# STB_USB.net
KiCad netlist of a schematic drawn in Altium Designer
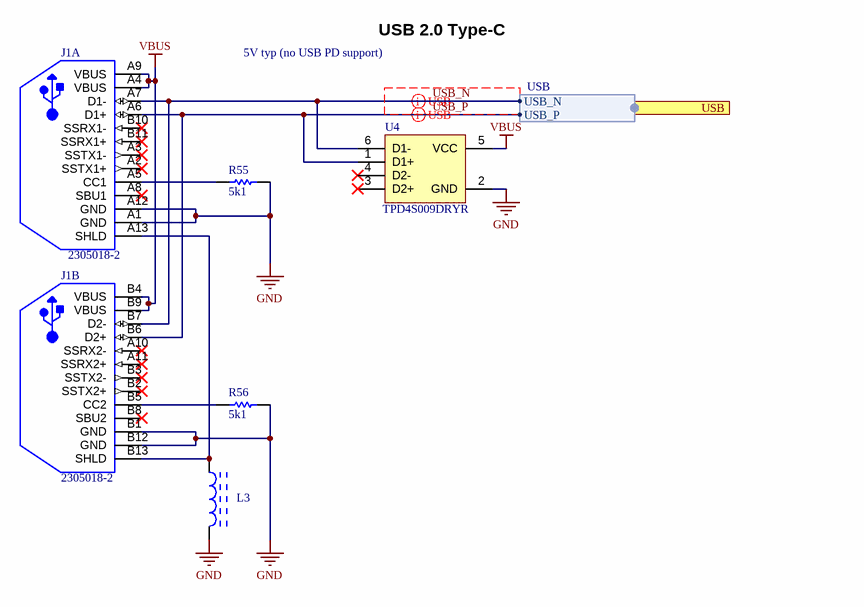
[diagram p0: STB_USB.SchDoc]

(export (version "E")
  (design (tool "Eeschema 10.0.6"))
  (components
    (comp (ref "J1")
      (value "2305018-2")
      (footprint "2305018-2")
      (description "USB TYPE C, REC IPX8 ON BOARD DUAL SMT")
      (fields (field (name "MANUFACTURER") "TE Connectivity"))
      (libsource (lib "") (part "632723300011_1"))
    )
    (comp (ref "L3")
      (value "LI0402E300R-10")
      (footprint "INDC1005X07L")
      (description "30 Ohm 1 Power, Signal Line Ferrite Bead 0402 (1005 Metric) 500mA 300 mOhm Max DCR")
      (fields (field (name "MANUFACTURER") "Laird-Signal Integrity Products"))
      (libsource (lib "ETHZ Vault") (part "Ferrite Bead"))
    )
    (comp (ref "R55")
      (value "5k1")
      (footprint "RESC1005X40X25LL05T10")
      (fields
        (field (name "PART NUMBER") "RC0402FR-075K1L")
        (field (name "MANUFACTURER") "Yageo / Phycomp")
        (field (name "TOLERANCE") "1%")
      )
      (libsource (lib "Altium Content Vault") (part "RES"))
    )
    (comp (ref "R56")
      (value "5k1")
      (footprint "RESC1005X40X25LL05T10")
      (fields
        (field (name "PART NUMBER") "RC0402FR-075K1L")
        (field (name "MANUFACTURER") "Yageo / Phycomp")
        (field (name "TOLERANCE") "1%")
      )
      (libsource (lib "Altium Content Vault") (part "RES"))
    )
    (comp (ref "U4")
      (value "TPD4S009DRYR")
      (footprint "DRY0006A")
      (fields (field (name "MANUFACTURER") "Texas Instruments"))
      (libsource (lib "Altium Content Vault") (part "TI-TPD4S009-SON_DRY-6"))
    )
  )
  (nets
    (net (code "2") (name "/USB_N") (class "Default")
      (node (ref "J1") (pin "A7") (pinfunction "D1-_A7") (pintype "bidirectional"))
      (node (ref "J1") (pin "B7") (pinfunction "D2-_B7") (pintype "bidirectional"))
      (node (ref "U4") (pin "6") (pinfunction "D1-_6") (pintype "passive"))
    )
    (net (code "3") (name "/USB_P") (class "Default")
      (node (ref "J1") (pin "A6") (pinfunction "D1+_A6") (pintype "bidirectional"))
      (node (ref "J1") (pin "B6") (pinfunction "D2+_B6") (pintype "bidirectional"))
      (node (ref "U4") (pin "1") (pinfunction "D1+_1") (pintype "passive"))
    )
    (net (code "5") (name "GND") (class "Default")
      (node (ref "J1") (pin "A1") (pinfunction "GND_A1") (pintype "power_in"))
      (node (ref "J1") (pin "A12") (pinfunction "GND_A12") (pintype "power_in"))
      (node (ref "J1") (pin "B1") (pinfunction "GND_B1") (pintype "power_in"))
      (node (ref "J1") (pin "B12") (pinfunction "GND_B12") (pintype "power_in"))
      (node (ref "L3") (pin "2") (pinfunction "2_2") (pintype "passive"))
      (node (ref "R55") (pin "1") (pinfunction "1_1") (pintype "passive"))
      (node (ref "R56") (pin "1") (pinfunction "1_1") (pintype "passive"))
      (node (ref "U4") (pin "2") (pinfunction "GND_2") (pintype "power_in"))
    )
    (net (code "6") (name "Net-(J1A-CC1)") (class "Default")
      (node (ref "J1") (pin "A5") (pinfunction "CC1_A5") (pintype "passive"))
      (node (ref "R55") (pin "2") (pinfunction "2_2") (pintype "passive"))
    )
    (net (code "7") (name "Net-(J1A-SHLD)") (class "Default")
      (node (ref "J1") (pin "A13") (pinfunction "SHLD_A13") (pintype "power_in"))
      (node (ref "J1") (pin "B13") (pinfunction "SHLD_B13") (pintype "power_in"))
      (node (ref "L3") (pin "1") (pinfunction "1_1") (pintype "passive"))
    )
    (net (code "8") (name "Net-(J1B-CC2)") (class "Default")
      (node (ref "J1") (pin "B5") (pinfunction "CC2_B5") (pintype "passive"))
      (node (ref "R56") (pin "2") (pinfunction "2_2") (pintype "passive"))
    )
    (net (code "9") (name "VBUS") (class "Default")
      (node (ref "J1") (pin "A4") (pinfunction "VBUS_A4") (pintype "power_in"))
      (node (ref "J1") (pin "A9") (pinfunction "VBUS_A9") (pintype "power_in"))
      (node (ref "J1") (pin "B4") (pinfunction "VBUS_B4") (pintype "power_in"))
      (node (ref "J1") (pin "B9") (pinfunction "VBUS_B9") (pintype "power_in"))
      (node (ref "U4") (pin "5") (pinfunction "VCC_5") (pintype "power_in"))
    )
    (net (code "10") (name "unconnected-(J1A-SBU1-PadA8)") (class "Default")
      (node (ref "J1") (pin "A8") (pinfunction "SBU1_A8") (pintype "passive+no_connect"))
    )
    (net (code "11") (name "unconnected-(J1A-SSRX1+-PadB11)") (class "Default")
      (node (ref "J1") (pin "B11") (pinfunction "SSRX1+_B11") (pintype "input+no_connect"))
    )
    (net (code "12") (name "unconnected-(J1A-SSRX1--PadB10)") (class "Default")
      (node (ref "J1") (pin "B10") (pinfunction "SSRX1-_B10") (pintype "input+no_connect"))
    )
    (net (code "13") (name "unconnected-(J1A-SSTX1+-PadA2)") (class "Default")
      (node (ref "J1") (pin "A2") (pinfunction "SSTX1+_A2") (pintype "output+no_connect"))
    )
    (net (code "14") (name "unconnected-(J1A-SSTX1--PadA3)") (class "Default")
      (node (ref "J1") (pin "A3") (pinfunction "SSTX1-_A3") (pintype "output+no_connect"))
    )
    (net (code "15") (name "unconnected-(J1B-SBU2-PadB8)") (class "Default")
      (node (ref "J1") (pin "B8") (pinfunction "SBU2_B8") (pintype "passive+no_connect"))
    )
    (net (code "16") (name "unconnected-(J1B-SSRX2+-PadA11)") (class "Default")
      (node (ref "J1") (pin "A11") (pinfunction "SSRX2+_A11") (pintype "input+no_connect"))
    )
    (net (code "17") (name "unconnected-(J1B-SSRX2--PadA10)") (class "Default")
      (node (ref "J1") (pin "A10") (pinfunction "SSRX2-_A10") (pintype "input+no_connect"))
    )
    (net (code "18") (name "unconnected-(J1B-SSTX2+-PadB2)") (class "Default")
      (node (ref "J1") (pin "B2") (pinfunction "SSTX2+_B2") (pintype "output+no_connect"))
    )
    (net (code "19") (name "unconnected-(J1B-SSTX2--PadB3)") (class "Default")
      (node (ref "J1") (pin "B3") (pinfunction "SSTX2-_B3") (pintype "output+no_connect"))
    )
    (net (code "20") (name "unconnected-(U4-D2+-Pad3)") (class "Default")
      (node (ref "U4") (pin "3") (pinfunction "D2+_3") (pintype "passive+no_connect"))
    )
    (net (code "21") (name "unconnected-(U4-D2--Pad4)") (class "Default")
      (node (ref "U4") (pin "4") (pinfunction "D2-_4") (pintype "passive+no_connect"))
    )
  )
)
